# AS5600.net
KiCad netlist of a schematic drawn in Altium Designer
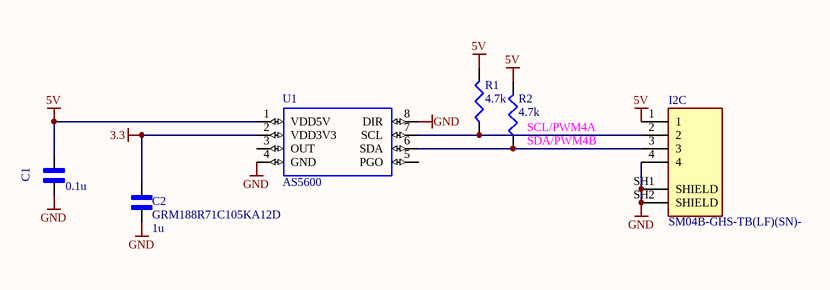
[diagram p0: AS5600.SchDoc]

(export (version "E")
  (design (tool "Eeschema 10.0.6"))
  (components
    (comp (ref "C1")
      (value "0.1u")
      (footprint "*CAPC1608X90")
      (description "Cap Thin Film 0.1uf 50v 0603")
      (fields (field (name "MF") "AVX") (field (name "MP") "GX035C104MAT2-500"))
      (libsource (lib "lib") (part "GX035C104MAT2-500"))
    )
    (comp (ref "C2")
      (value "GRM188R71C105KA12D")
      (footprint "CAPC1608X90N")
      (description "SMD Capacitor X7R(EIA) with Capacitance: 1.0uF Tol. 10%. Rated Voltage: 16Vdc")
      (fields (field (name "MF") "Murata Electronics") (field (name "ALTIUM_VALUE") "1u"))
      (libsource (lib "lib") (part "GRM188R71C105KA12D"))
    )
    (comp (ref "I2C")
      (value "SM04B-GHS-TB(LF)(SN)-")
      (footprint "JST_SM04B-GHS-TB(LF)(SN)-")
      (description "Connector Header Surface Mount, Right Angle 4 position 0.049 _1.25mm_")
      (fields (field (name "MP") "SM04B-GHS-TB(LF)(SN)") (field (name "MF") "JST Sales"))
      (libsource (lib "lib") (part "SM04B-GHS-TB(LF)(SN)-"))
    )
    (comp (ref "R1")
      (value "4.7k")
      (footprint "J1-0603")
      (description "4.7 kOhms ±1% 0.1W, 1/10W Chip Resistor 0603 (1608 Metric) Thick Film")
      (fields (field (name "MF") "Yageo or NXP") (field (name "MP") "RC0603FR-074K7L"))
      (libsource (lib "lib") (part "RC0603FR-074K7L"))
    )
    (comp (ref "R2")
      (value "4.7k")
      (footprint "J1-0603")
      (description "4.7 kOhms ±1% 0.1W, 1/10W Chip Resistor 0603 (1608 Metric) Thick Film")
      (fields (field (name "MF") "Yageo or NXP") (field (name "MP") "RC0603FR-074K7L"))
      (libsource (lib "lib") (part "RC0603FR-074K7L"))
    )
    (comp (ref "U1")
      (value "AS5600")
      (footprint "SOIC127P600X175-8N")
      (description "Hall Effect Sensor Angle External Magnet, Not Included Gull Wing")
      (fields (field (name "MF") "ams"))
      (libsource (lib "lib") (part "AS5600"))
    )
  )
  (nets
    (net (code "1") (name "/SCL{slash}PWM4A") (class "Default")
      (node (ref "I2C") (pin "2") (pinfunction "2_2") (pintype "passive"))
      (node (ref "R1") (pin "1") (pinfunction "1_1") (pintype "passive"))
      (node (ref "U1") (pin "7") (pinfunction "SCL_7") (pintype "bidirectional"))
    )
    (net (code "2") (name "/SDA{slash}PWM4B") (class "Default")
      (node (ref "I2C") (pin "3") (pinfunction "3_3") (pintype "passive"))
      (node (ref "R2") (pin "1") (pinfunction "1_1") (pintype "passive"))
      (node (ref "U1") (pin "6") (pinfunction "SDA_6") (pintype "bidirectional"))
    )
    (net (code "3") (name "3.3") (class "Default")
      (node (ref "C2") (pin "2") (pinfunction "2_2") (pintype "passive"))
      (node (ref "U1") (pin "2") (pinfunction "VDD3V3_2") (pintype "bidirectional"))
    )
    (net (code "4") (name "5V") (class "Default")
      (node (ref "C1") (pin "1") (pinfunction "1_1") (pintype "passive"))
      (node (ref "I2C") (pin "1") (pinfunction "1_1") (pintype "passive"))
      (node (ref "R1") (pin "2") (pinfunction "2_2") (pintype "passive"))
      (node (ref "R2") (pin "2") (pinfunction "2_2") (pintype "passive"))
      (node (ref "U1") (pin "1") (pinfunction "VDD5V_1") (pintype "bidirectional"))
    )
    (net (code "5") (name "GND") (class "Default")
      (node (ref "C1") (pin "2") (pinfunction "2_2") (pintype "passive"))
      (node (ref "C2") (pin "1") (pinfunction "1_1") (pintype "passive"))
      (node (ref "I2C") (pin "4") (pinfunction "4_4") (pintype "passive"))
      (node (ref "I2C") (pin "SH1") (pinfunction "SHIELD_SH1") (pintype "power_in"))
      (node (ref "I2C") (pin "SH2") (pinfunction "SHIELD_SH2") (pintype "power_in"))
      (node (ref "U1") (pin "4") (pinfunction "GND_4") (pintype "bidirectional"))
      (node (ref "U1") (pin "8") (pinfunction "DIR_8") (pintype "bidirectional"))
    )
    (net (code "6") (name "unconnected-(U1-OUT-Pad3)") (class "Default")
      (node (ref "U1") (pin "3") (pinfunction "OUT_3") (pintype "bidirectional"))
    )
    (net (code "7") (name "unconnected-(U1-PGO-Pad5)") (class "Default")
      (node (ref "U1") (pin "5") (pinfunction "PGO_5") (pintype "bidirectional"))
    )
  )
)
